# 261003902xxxx-HW-V1_3.net
KiCad netlist of a schematic drawn in EAGLE
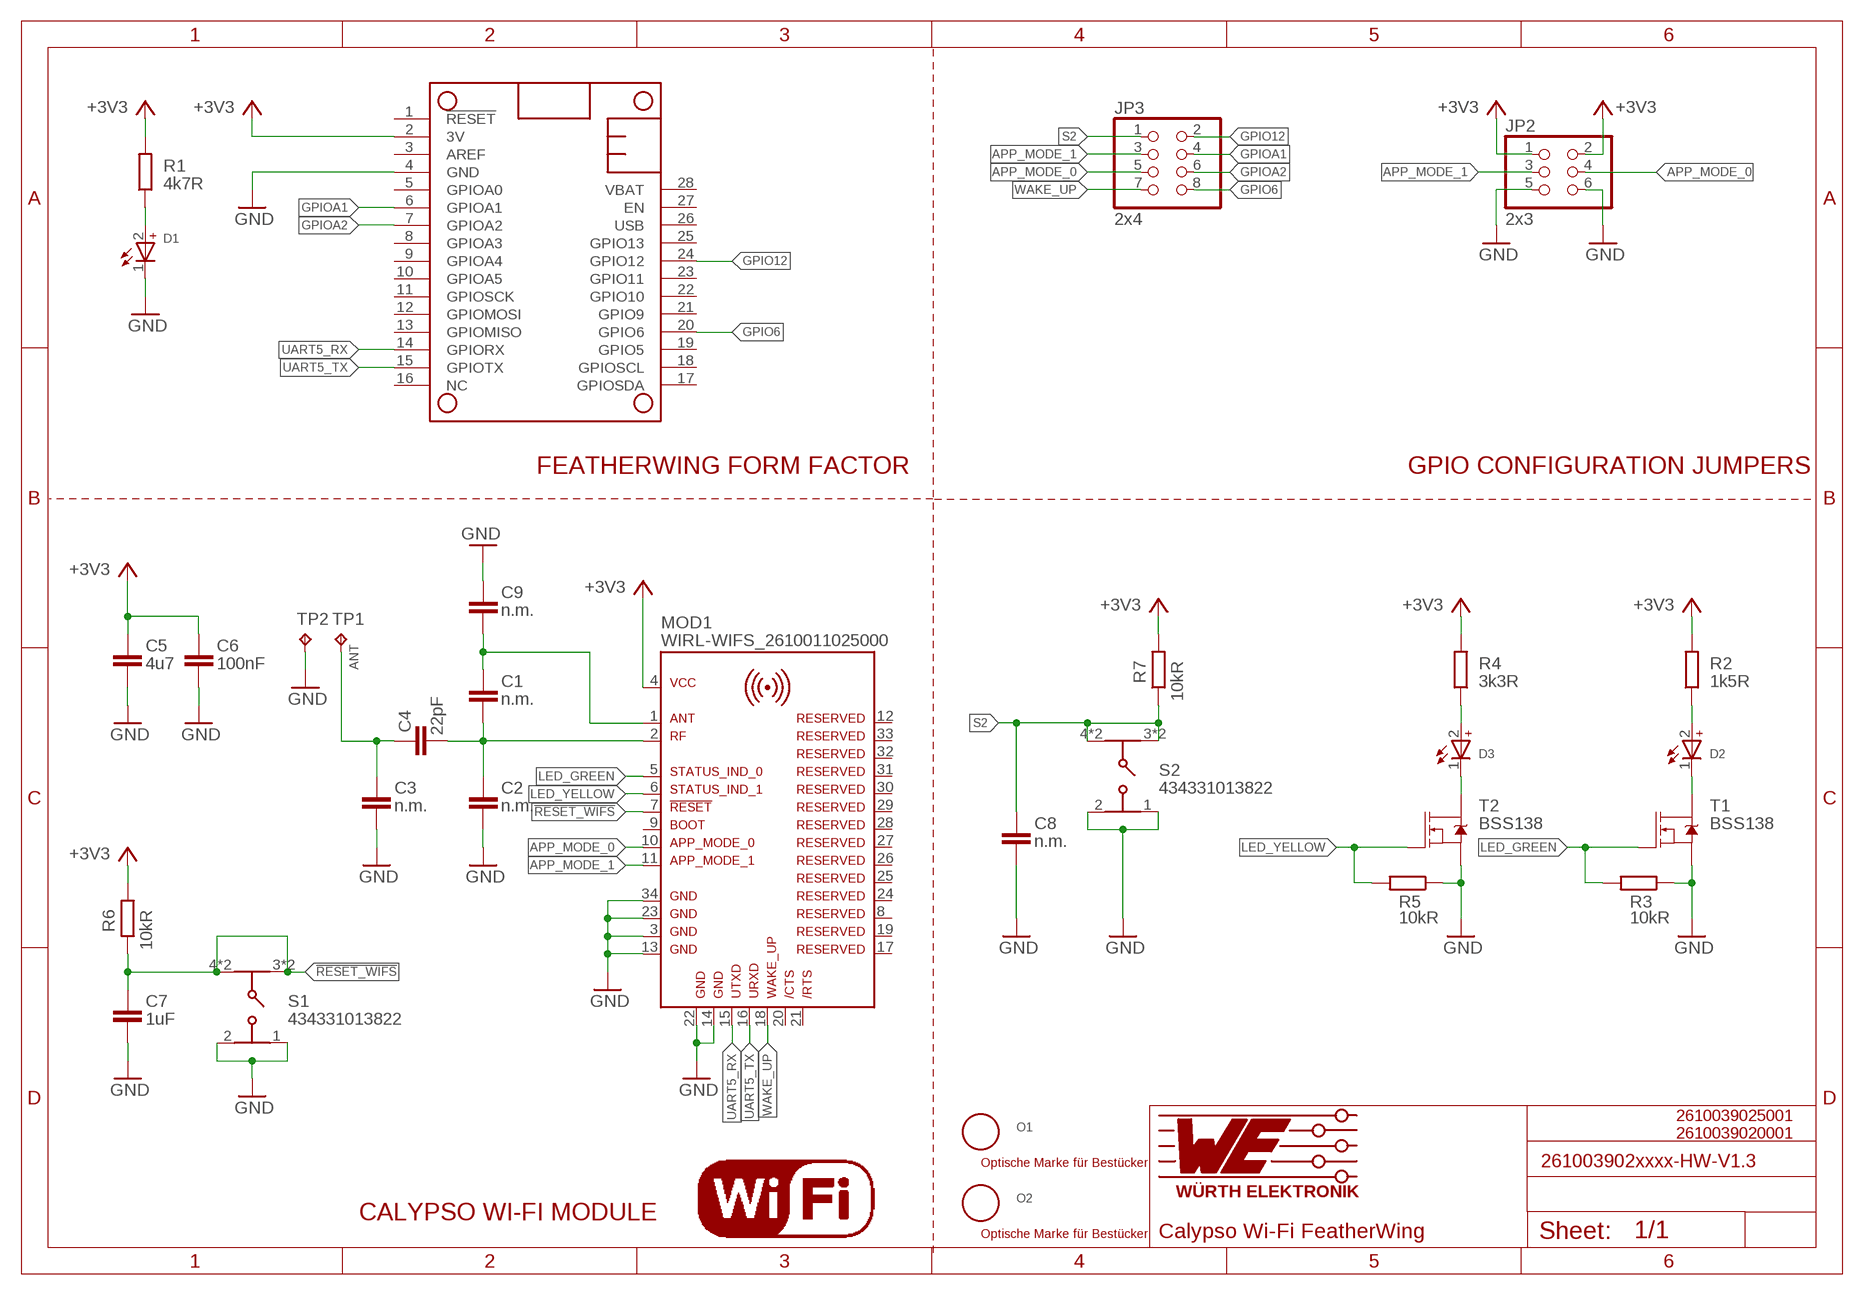
[diagram p0: schematic, sheet 1]

(export (version "E")
  (design (tool "Eeschema 10.0.6"))
  (components
    (comp (ref "C1")
      (value "n.m.")
      (footprint "eagle-import:C0402_IPC")
      (libsource (lib "eagle-import") (part "rcl-amber_C0402_IPC"))
    )
    (comp (ref "C2")
      (value "n.m.")
      (footprint "eagle-import:C0201_IPC")
      (libsource (lib "eagle-import") (part "rcl-amber_C0201_IPC"))
    )
    (comp (ref "C3")
      (value "n.m.")
      (footprint "eagle-import:C0201_IPC")
      (libsource (lib "eagle-import") (part "rcl-amber_C0201_IPC"))
    )
    (comp (ref "C4")
      (value "22pF")
      (footprint "eagle-import:C0402_IPC")
      (fields (field (name "MANUFACTURER") "Würth Elektronik"))
      (libsource (lib "eagle-import") (part "C0402_IPC22PF"))
    )
    (comp (ref "C5")
      (value "4u7")
      (footprint "eagle-import:C0402_IPC")
      (fields (field (name "MANUFACTURER") "Würth Elektronik"))
      (libsource (lib "eagle-import") (part "C0402_IPC4.7UF"))
    )
    (comp (ref "C6")
      (value "100nF")
      (footprint "eagle-import:C0402_IPC")
      (fields (field (name "MANUFACTURER") "Würth Elektronik"))
      (libsource (lib "eagle-import") (part "C0402_IPC100NF"))
    )
    (comp (ref "C7")
      (value "1uF")
      (footprint "eagle-import:C0402_IPC")
      (fields (field (name "MANUFACTURER") "Würth Elektronik"))
      (libsource (lib "eagle-import") (part "C0402_IPC1UF"))
    )
    (comp (ref "C8")
      (value "n.m.")
      (footprint "eagle-import:C0402_IPC")
      (libsource (lib "eagle-import") (part "rcl-amber_C0402_IPC"))
    )
    (comp (ref "C9")
      (value "n.m.")
      (footprint "eagle-import:C0201_IPC")
      (libsource (lib "eagle-import") (part "rcl-amber_C0201_IPC"))
    )
    (comp (ref "D1")
      (value "RED")
      (footprint "eagle-import:WL-SMSW_1204_A")
      (fields (field (name "MANUFACTURER") "Würth Elektronik"))
      (libsource (lib "eagle-import") (part "WL-SMSW_1204_155124RS73200"))
    )
    (comp (ref "D2")
      (value "GREEN")
      (footprint "eagle-import:WL-SMSW_1204_A")
      (fields (field (name "MANUFACTURER") "Würth Elektronik"))
      (libsource (lib "eagle-import") (part "WL-SMSW_1204_155124VS73200"))
    )
    (comp (ref "D3")
      (value "YELLOW")
      (footprint "eagle-import:WL-SMSW_1204_A")
      (fields (field (name "MANUFACTURER") "Würth Elektronik"))
      (libsource (lib "eagle-import") (part "WL-SMSW_1204_155124YS73200"))
    )
    (comp (ref "JP2")
      (value "2x3")
      (footprint "eagle-import:2X03")
      (fields (field (name "MANUFACTURER") "Würth Elektronik"))
      (libsource (lib "eagle-import") (part "PINHD-2X3"))
    )
    (comp (ref "JP3")
      (value "2x4")
      (footprint "eagle-import:2X04")
      (fields (field (name "MANUFACTURER") "Würth Elektronik"))
      (libsource (lib "eagle-import") (part "PINHD-2X4"))
    )
    (comp (ref "MOD1")
      (value "WIRL-WIFS_2610011025000")
      (footprint "eagle-import:WIRL-WIFS_2610011025000")
      (fields (field (name "MANUFACTURER") "Würth Elektronik"))
      (libsource (lib "eagle-import") (part "WIRL-WIFS_2610011025000"))
    )
    (comp (ref "MS1")
      (value "header: 1 x 12 & 1 x 16")
      (footprint "eagle-import:FEATHERWING_80MM")
      (fields (field (name "COMMENT") "Kit containing 2 headers") (field (name "MANUFACTURER") "Adafruit"))
      (libsource (lib "eagle-import") (part "FEATHERWING_80MM"))
    )
    (comp (ref "O1")
      (value "n.m.")
      (footprint "eagle-import:OPTISCHE_MARKE")
      (libsource (lib "eagle-import") (part "OPT_MARKE"))
    )
    (comp (ref "O2")
      (value "n.m.")
      (footprint "eagle-import:OPTISCHE_MARKE")
      (libsource (lib "eagle-import") (part "OPT_MARKE"))
    )
    (comp (ref "R1")
      (value "4k7R")
      (footprint "eagle-import:R0402_IPC")
      (fields (field (name "MANUFACTURER") "Yageo"))
      (libsource (lib "eagle-import") (part "R0402_IPC4K7"))
    )
    (comp (ref "R2")
      (value "1k5R")
      (footprint "eagle-import:R0402_IPC")
      (fields (field (name "MANUFACTURER") "Yageo"))
      (libsource (lib "eagle-import") (part "R0402_IPC1K5R"))
    )
    (comp (ref "R3")
      (value "10kR")
      (footprint "eagle-import:R0402_IPC")
      (fields (field (name "MANUFACTURER") "Yageo"))
      (libsource (lib "eagle-import") (part "R0402_IPC10KR"))
    )
    (comp (ref "R4")
      (value "3k3R")
      (footprint "eagle-import:R0402_IPC")
      (fields (field (name "MANUFACTURER") "Yageo"))
      (libsource (lib "eagle-import") (part "R0402_IPC3K3R"))
    )
    (comp (ref "R5")
      (value "10kR")
      (footprint "eagle-import:R0402_IPC")
      (fields (field (name "MANUFACTURER") "Yageo"))
      (libsource (lib "eagle-import") (part "R0402_IPC10KR"))
    )
    (comp (ref "R6")
      (value "10kR")
      (footprint "eagle-import:R0402_IPC")
      (fields (field (name "MANUFACTURER") "Yageo"))
      (libsource (lib "eagle-import") (part "R0402_IPC10KR"))
    )
    (comp (ref "R7")
      (value "10kR")
      (footprint "eagle-import:R0402_IPC")
      (fields (field (name "MANUFACTURER") "Yageo"))
      (libsource (lib "eagle-import") (part "R0402_IPC10KR"))
    )
    (comp (ref "S1")
      (value "434331013822")
      (footprint "eagle-import:434331013822")
      (fields (field (name "MANUFACTURER") "Würth Elektronik"))
      (libsource (lib "eagle-import") (part "434331013822"))
    )
    (comp (ref "S2")
      (value "434331013822")
      (footprint "eagle-import:434331013822")
      (fields (field (name "MANUFACTURER") "Würth Elektronik"))
      (libsource (lib "eagle-import") (part "434331013822"))
    )
    (comp (ref "T1")
      (value "BSS138")
      (footprint "eagle-import:SOT23-3")
      (fields (field (name "MANUFACTURER") "Diodes Incorporated"))
      (libsource (lib "eagle-import") (part "MOSFET-NCH-BSS138"))
    )
    (comp (ref "T2")
      (value "BSS138")
      (footprint "eagle-import:SOT23-3")
      (fields (field (name "MANUFACTURER") "Diodes Incorporated"))
      (libsource (lib "eagle-import") (part "MOSFET-NCH-BSS138"))
    )
    (comp (ref "TP1")
      (value "n.m.")
      (footprint "eagle-import:D0.6")
      (libsource (lib "eagle-import") (part "TP-DRILL0.6"))
    )
    (comp (ref "TP2")
      (value "n.m.")
      (footprint "eagle-import:D0.6")
      (libsource (lib "eagle-import") (part "TP-DRILL0.6"))
    )
    (comp (ref "U$1")
      (value "WIFI5MM")
      (footprint "eagle-import:WIFI_5MM")
      (libsource (lib "eagle-import") (part "WIFI5MM"))
    )
  )
  (nets
    (net (code "1") (name "+3V3") (class "Default")
      (node (ref "C5") (pin "1") (pinfunction "1_1") (pintype "passive"))
      (node (ref "C6") (pin "1") (pinfunction "1_1") (pintype "passive"))
      (node (ref "JP2") (pin "1") (pinfunction "1_1") (pintype "passive"))
      (node (ref "JP2") (pin "2") (pinfunction "2_2") (pintype "passive"))
      (node (ref "MOD1") (pin "4") (pinfunction "4_4") (pintype "passive"))
      (node (ref "MS1") (pin "2") (pinfunction "3V_2") (pintype "power_in"))
      (node (ref "R1") (pin "2") (pinfunction "2_2") (pintype "passive"))
      (node (ref "R2") (pin "2") (pinfunction "2_2") (pintype "passive"))
      (node (ref "R4") (pin "2") (pinfunction "2_2") (pintype "passive"))
      (node (ref "R6") (pin "2") (pinfunction "2_2") (pintype "passive"))
      (node (ref "R7") (pin "2") (pinfunction "2_2") (pintype "passive"))
    )
    (net (code "2") (name "/ANT") (class "Default")
      (node (ref "C3") (pin "P$1") (pinfunction "1_P$1") (pintype "passive"))
      (node (ref "C4") (pin "1") (pinfunction "1_1") (pintype "passive"))
      (node (ref "TP1") (pin "P$1") (pinfunction "TP_P$1") (pintype "input"))
    )
    (net (code "3") (name "/USB") (class "Default")
      (node (ref "MS1") (pin "26") (pinfunction "USB_26") (pintype "power_in"))
    )
    (net (code "4") (name "/VBAT") (class "Default")
      (node (ref "MS1") (pin "28") (pinfunction "VBAT_28") (pintype "power_in"))
    )
    (net (code "5") (name "/~{RESET_WIFS}") (class "Default")
      (node (ref "C7") (pin "1") (pinfunction "1_1") (pintype "passive"))
      (node (ref "MOD1") (pin "7") (pinfunction "7_7") (pintype "input"))
      (node (ref "R6") (pin "1") (pinfunction "1_1") (pintype "passive"))
      (node (ref "S1") (pin "3") (pinfunction "3_3") (pintype "passive"))
      (node (ref "S1") (pin "4") (pinfunction "4_4") (pintype "passive"))
      (node (ref "S1") (pin "5") (pinfunction "3_5") (pintype "passive"))
      (node (ref "S1") (pin "6") (pinfunction "4_6") (pintype "passive"))
    )
    (net (code "6") (name "APP_MODE_0") (class "Default")
      (node (ref "JP2") (pin "4") (pinfunction "4_4") (pintype "passive"))
      (node (ref "JP3") (pin "5") (pinfunction "5_5") (pintype "passive"))
      (node (ref "MOD1") (pin "10") (pinfunction "10_10") (pintype "input"))
    )
    (net (code "7") (name "APP_MODE_1") (class "Default")
      (node (ref "JP2") (pin "3") (pinfunction "3_3") (pintype "passive"))
      (node (ref "JP3") (pin "3") (pinfunction "3_3") (pintype "passive"))
      (node (ref "MOD1") (pin "11") (pinfunction "11_11") (pintype "input"))
    )
    (net (code "8") (name "GND") (class "Default")
      (node (ref "C2") (pin "P$2") (pinfunction "2_P$2") (pintype "passive"))
      (node (ref "C3") (pin "P$2") (pinfunction "2_P$2") (pintype "passive"))
      (node (ref "C5") (pin "2") (pinfunction "2_2") (pintype "passive"))
      (node (ref "C6") (pin "2") (pinfunction "2_2") (pintype "passive"))
      (node (ref "C7") (pin "2") (pinfunction "2_2") (pintype "passive"))
      (node (ref "C8") (pin "2") (pinfunction "2_2") (pintype "passive"))
      (node (ref "C9") (pin "P$2") (pinfunction "2_P$2") (pintype "passive"))
      (node (ref "D1") (pin "1") (pinfunction "-_1") (pintype "passive"))
      (node (ref "JP2") (pin "5") (pinfunction "5_5") (pintype "passive"))
      (node (ref "JP2") (pin "6") (pinfunction "6_6") (pintype "passive"))
      (node (ref "MOD1") (pin "13") (pinfunction "13_13") (pintype "passive"))
      (node (ref "MOD1") (pin "14") (pinfunction "14_14") (pintype "passive"))
      (node (ref "MOD1") (pin "22") (pinfunction "22_22") (pintype "passive"))
      (node (ref "MOD1") (pin "23") (pinfunction "23_23") (pintype "passive"))
      (node (ref "MOD1") (pin "3") (pinfunction "3_3") (pintype "passive"))
      (node (ref "MOD1") (pin "34") (pinfunction "34_34") (pintype "passive"))
      (node (ref "MS1") (pin "4") (pinfunction "GND_4") (pintype "power_in"))
      (node (ref "R3") (pin "1") (pinfunction "1_1") (pintype "passive"))
      (node (ref "R5") (pin "1") (pinfunction "1_1") (pintype "passive"))
      (node (ref "S1") (pin "1") (pinfunction "1_1") (pintype "passive"))
      (node (ref "S1") (pin "2") (pinfunction "2_2") (pintype "passive"))
      (node (ref "S2") (pin "1") (pinfunction "1_1") (pintype "passive"))
      (node (ref "S2") (pin "2") (pinfunction "2_2") (pintype "passive"))
      (node (ref "T1") (pin "2") (pinfunction "S_2") (pintype "bidirectional"))
      (node (ref "T2") (pin "2") (pinfunction "S_2") (pintype "bidirectional"))
      (node (ref "TP2") (pin "P$1") (pinfunction "TP_P$1") (pintype "input"))
    )
    (net (code "9") (name "GPIO6") (class "Default")
      (node (ref "JP3") (pin "8") (pinfunction "8_8") (pintype "passive"))
      (node (ref "MS1") (pin "20") (pinfunction "GPIO6_20") (pintype "bidirectional"))
    )
    (net (code "10") (name "GPIO12") (class "Default")
      (node (ref "JP3") (pin "2") (pinfunction "2_2") (pintype "passive"))
      (node (ref "MS1") (pin "24") (pinfunction "GPIO12_24") (pintype "bidirectional"))
    )
    (net (code "11") (name "GPIOA1") (class "Default")
      (node (ref "JP3") (pin "4") (pinfunction "4_4") (pintype "passive"))
      (node (ref "MS1") (pin "6") (pinfunction "GPIOA1_6") (pintype "bidirectional"))
    )
    (net (code "12") (name "GPIOA2") (class "Default")
      (node (ref "JP3") (pin "6") (pinfunction "6_6") (pintype "passive"))
      (node (ref "MS1") (pin "7") (pinfunction "GPIOA2_7") (pintype "bidirectional"))
    )
    (net (code "13") (name "LED_GREEN") (class "Default")
      (node (ref "MOD1") (pin "5") (pinfunction "5_5") (pintype "output"))
      (node (ref "R3") (pin "2") (pinfunction "2_2") (pintype "passive"))
      (node (ref "T1") (pin "1") (pinfunction "G_1") (pintype "bidirectional"))
    )
    (net (code "14") (name "LED_YELLOW") (class "Default")
      (node (ref "MOD1") (pin "6") (pinfunction "6_6") (pintype "output"))
      (node (ref "R5") (pin "2") (pinfunction "2_2") (pintype "passive"))
      (node (ref "T2") (pin "1") (pinfunction "G_1") (pintype "bidirectional"))
    )
    (net (code "15") (name "Net-(C2-1)") (class "Default")
      (node (ref "C1") (pin "1") (pinfunction "1_1") (pintype "passive"))
      (node (ref "C2") (pin "P$1") (pinfunction "1_P$1") (pintype "passive"))
      (node (ref "C4") (pin "2") (pinfunction "2_2") (pintype "passive"))
      (node (ref "MOD1") (pin "2") (pinfunction "2_2") (pintype "passive"))
    )
    (net (code "16") (name "Net-(C9-1)") (class "Default")
      (node (ref "C1") (pin "2") (pinfunction "2_2") (pintype "passive"))
      (node (ref "C9") (pin "P$1") (pinfunction "1_P$1") (pintype "passive"))
      (node (ref "MOD1") (pin "1") (pinfunction "1_1") (pintype "passive"))
    )
    (net (code "17") (name "Net-(D1-+)") (class "Default")
      (node (ref "D1") (pin "2") (pinfunction "+_2") (pintype "passive"))
      (node (ref "R1") (pin "1") (pinfunction "1_1") (pintype "passive"))
    )
    (net (code "18") (name "Net-(D2-+)") (class "Default")
      (node (ref "D2") (pin "2") (pinfunction "+_2") (pintype "passive"))
      (node (ref "R2") (pin "1") (pinfunction "1_1") (pintype "passive"))
    )
    (net (code "19") (name "Net-(D2--)") (class "Default")
      (node (ref "D2") (pin "1") (pinfunction "-_1") (pintype "passive"))
      (node (ref "T1") (pin "3") (pinfunction "D_3") (pintype "bidirectional"))
    )
    (net (code "20") (name "Net-(D3-+)") (class "Default")
      (node (ref "D3") (pin "2") (pinfunction "+_2") (pintype "passive"))
      (node (ref "R4") (pin "1") (pinfunction "1_1") (pintype "passive"))
    )
    (net (code "21") (name "Net-(D3--)") (class "Default")
      (node (ref "D3") (pin "1") (pinfunction "-_1") (pintype "passive"))
      (node (ref "T2") (pin "3") (pinfunction "D_3") (pintype "bidirectional"))
    )
    (net (code "22") (name "S2") (class "Default")
      (node (ref "C8") (pin "1") (pinfunction "1_1") (pintype "passive"))
      (node (ref "JP3") (pin "1") (pinfunction "1_1") (pintype "passive"))
      (node (ref "R7") (pin "1") (pinfunction "1_1") (pintype "passive"))
      (node (ref "S2") (pin "3") (pinfunction "3_3") (pintype "passive"))
      (node (ref "S2") (pin "4") (pinfunction "4_4") (pintype "passive"))
      (node (ref "S2") (pin "5") (pinfunction "3_5") (pintype "passive"))
      (node (ref "S2") (pin "6") (pinfunction "4_6") (pintype "passive"))
    )
    (net (code "23") (name "UART5_RX") (class "Default")
      (node (ref "MOD1") (pin "15") (pinfunction "15_15") (pintype "output"))
      (node (ref "MS1") (pin "14") (pinfunction "GPIORX_14") (pintype "bidirectional"))
    )
    (net (code "24") (name "UART5_TX") (class "Default")
      (node (ref "MOD1") (pin "16") (pinfunction "16_16") (pintype "input"))
      (node (ref "MS1") (pin "15") (pinfunction "GPIOTX_15") (pintype "bidirectional"))
    )
    (net (code "25") (name "WAKE_UP") (class "Default")
      (node (ref "JP3") (pin "7") (pinfunction "7_7") (pintype "passive"))
      (node (ref "MOD1") (pin "18") (pinfunction "18_18") (pintype "input"))
    )
    (net (code "26") (name "unconnected-(MOD1-Pad8)") (class "Default")
      (node (ref "MOD1") (pin "8") (pinfunction "8_8") (pintype "passive"))
    )
    (net (code "27") (name "unconnected-(MOD1-Pad9)") (class "Default")
      (node (ref "MOD1") (pin "9") (pinfunction "9_9") (pintype "input"))
    )
    (net (code "28") (name "unconnected-(MOD1-Pad12)") (class "Default")
      (node (ref "MOD1") (pin "12") (pinfunction "12_12") (pintype "passive"))
    )
    (net (code "29") (name "unconnected-(MOD1-Pad17)") (class "Default")
      (node (ref "MOD1") (pin "17") (pinfunction "17_17") (pintype "passive"))
    )
    (net (code "30") (name "unconnected-(MOD1-Pad19)") (class "Default")
      (node (ref "MOD1") (pin "19") (pinfunction "19_19") (pintype "passive"))
    )
    (net (code "31") (name "unconnected-(MOD1-Pad20)") (class "Default")
      (node (ref "MOD1") (pin "20") (pinfunction "20_20") (pintype "input"))
    )
    (net (code "32") (name "unconnected-(MOD1-Pad21)") (class "Default")
      (node (ref "MOD1") (pin "21") (pinfunction "21_21") (pintype "output"))
    )
    (net (code "33") (name "unconnected-(MOD1-Pad24)") (class "Default")
      (node (ref "MOD1") (pin "24") (pinfunction "24_24") (pintype "passive"))
    )
    (net (code "34") (name "unconnected-(MOD1-Pad25)") (class "Default")
      (node (ref "MOD1") (pin "25") (pinfunction "25_25") (pintype "passive"))
    )
    (net (code "35") (name "unconnected-(MOD1-Pad26)") (class "Default")
      (node (ref "MOD1") (pin "26") (pinfunction "26_26") (pintype "passive"))
    )
    (net (code "36") (name "unconnected-(MOD1-Pad27)") (class "Default")
      (node (ref "MOD1") (pin "27") (pinfunction "27_27") (pintype "passive"))
    )
    (net (code "37") (name "unconnected-(MOD1-Pad28)") (class "Default")
      (node (ref "MOD1") (pin "28") (pinfunction "28_28") (pintype "passive"))
    )
    (net (code "38") (name "unconnected-(MOD1-Pad29)") (class "Default")
      (node (ref "MOD1") (pin "29") (pinfunction "29_29") (pintype "passive"))
    )
    (net (code "39") (name "unconnected-(MOD1-Pad30)") (class "Default")
      (node (ref "MOD1") (pin "30") (pinfunction "30_30") (pintype "passive"))
    )
    (net (code "40") (name "unconnected-(MOD1-Pad31)") (class "Default")
      (node (ref "MOD1") (pin "31") (pinfunction "31_31") (pintype "passive"))
    )
    (net (code "41") (name "unconnected-(MOD1-Pad32)") (class "Default")
      (node (ref "MOD1") (pin "32") (pinfunction "32_32") (pintype "passive"))
    )
    (net (code "42") (name "unconnected-(MOD1-Pad33)") (class "Default")
      (node (ref "MOD1") (pin "33") (pinfunction "33_33") (pintype "passive"))
    )
    (net (code "43") (name "unconnected-(MS1-AREF-Pad3)") (class "Default")
      (node (ref "MS1") (pin "3") (pinfunction "AREF_3") (pintype "passive"))
    )
    (net (code "44") (name "unconnected-(MS1-EN-Pad27)") (class "Default")
      (node (ref "MS1") (pin "27") (pinfunction "EN_27") (pintype "passive"))
    )
    (net (code "45") (name "unconnected-(MS1-GPIO5-Pad19)") (class "Default")
      (node (ref "MS1") (pin "19") (pinfunction "GPIO5_19") (pintype "bidirectional"))
    )
    (net (code "46") (name "unconnected-(MS1-GPIO9-Pad21)") (class "Default")
      (node (ref "MS1") (pin "21") (pinfunction "GPIO9_21") (pintype "bidirectional"))
    )
    (net (code "47") (name "unconnected-(MS1-GPIO10-Pad22)") (class "Default")
      (node (ref "MS1") (pin "22") (pinfunction "GPIO10_22") (pintype "bidirectional"))
    )
    (net (code "48") (name "unconnected-(MS1-GPIO11-Pad23)") (class "Default")
      (node (ref "MS1") (pin "23") (pinfunction "GPIO11_23") (pintype "bidirectional"))
    )
    (net (code "49") (name "unconnected-(MS1-GPIO13-Pad25)") (class "Default")
      (node (ref "MS1") (pin "25") (pinfunction "GPIO13_25") (pintype "bidirectional"))
    )
    (net (code "50") (name "unconnected-(MS1-GPIOA0-Pad5)") (class "Default")
      (node (ref "MS1") (pin "5") (pinfunction "GPIOA0_5") (pintype "bidirectional"))
    )
    (net (code "51") (name "unconnected-(MS1-GPIOA3-Pad8)") (class "Default")
      (node (ref "MS1") (pin "8") (pinfunction "GPIOA3_8") (pintype "bidirectional"))
    )
    (net (code "52") (name "unconnected-(MS1-GPIOA4-Pad9)") (class "Default")
      (node (ref "MS1") (pin "9") (pinfunction "GPIOA4_9") (pintype "bidirectional"))
    )
    (net (code "53") (name "unconnected-(MS1-GPIOA5-Pad10)") (class "Default")
      (node (ref "MS1") (pin "10") (pinfunction "GPIOA5_10") (pintype "bidirectional"))
    )
    (net (code "54") (name "unconnected-(MS1-GPIOMISO-Pad13)") (class "Default")
      (node (ref "MS1") (pin "13") (pinfunction "GPIOMISO_13") (pintype "bidirectional"))
    )
    (net (code "55") (name "unconnected-(MS1-GPIOMOSI-Pad12)") (class "Default")
      (node (ref "MS1") (pin "12") (pinfunction "GPIOMOSI_12") (pintype "bidirectional"))
    )
    (net (code "56") (name "unconnected-(MS1-GPIOSCK-Pad11)") (class "Default")
      (node (ref "MS1") (pin "11") (pinfunction "GPIOSCK_11") (pintype "bidirectional"))
    )
    (net (code "57") (name "unconnected-(MS1-GPIOSCL-Pad18)") (class "Default")
      (node (ref "MS1") (pin "18") (pinfunction "GPIOSCL_18") (pintype "bidirectional"))
    )
    (net (code "58") (name "unconnected-(MS1-GPIOSDA-Pad17)") (class "Default")
      (node (ref "MS1") (pin "17") (pinfunction "GPIOSDA_17") (pintype "bidirectional"))
    )
    (net (code "59") (name "unconnected-(MS1-NC-Pad16)") (class "Default")
      (node (ref "MS1") (pin "16") (pinfunction "NC_16") (pintype "passive"))
    )
    (net (code "60") (name "unconnected-(MS1-~{RESET}-Pad1)") (class "Default")
      (node (ref "MS1") (pin "1") (pinfunction "~{RESET}_1") (pintype "input"))
    )
  )
)
